# solar_cell.net
KiCad netlist of a schematic drawn in Altium Designer
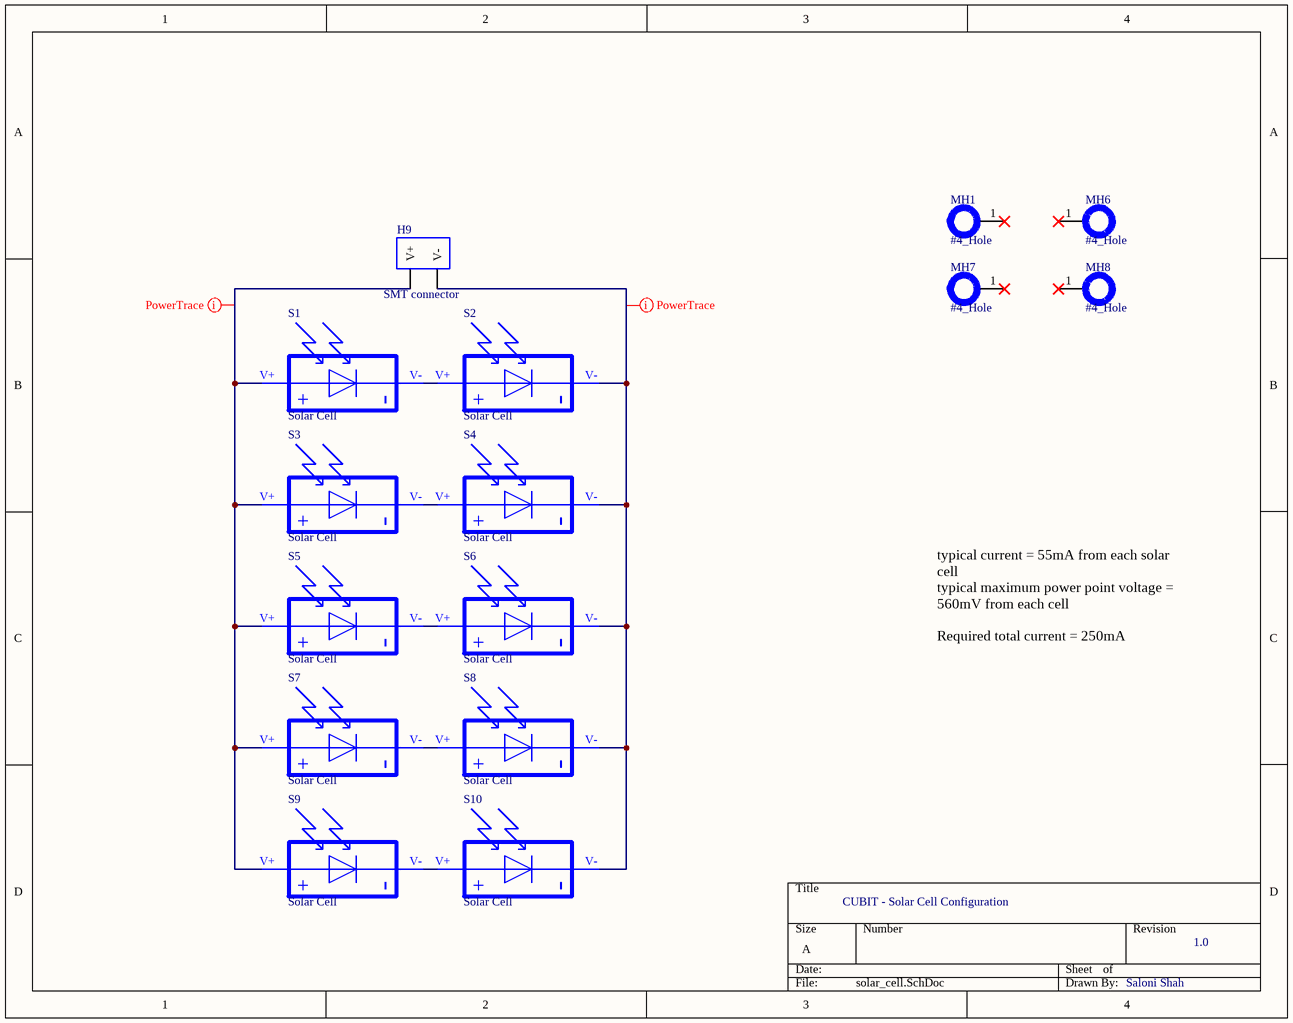
[diagram p0: solar_cell.SchDoc]

(export (version "E")
  (design (tool "Eeschema 10.0.6"))
  (components
    (comp (ref "H9")
      (value "SMT connector")
      (footprint "BAT_CONN")
      (description "2.00mm Pitch")
      (libsource (lib "LPEDT_proj_lib") (part "batt_conn_pad"))
    )
    (comp (ref "MH1")
      (value "#4_Hole")
      (footprint "HOLE_#4")
      (libsource (lib "LPEDT_proj_lib") (part "Mechanical_Hole"))
    )
    (comp (ref "MH6")
      (value "#4_Hole")
      (footprint "HOLE_#4")
      (libsource (lib "LPEDT_proj_lib") (part "Mechanical_Hole"))
    )
    (comp (ref "MH7")
      (value "#4_Hole")
      (footprint "HOLE_#4")
      (libsource (lib "LPEDT_proj_lib") (part "Mechanical_Hole"))
    )
    (comp (ref "MH8")
      (value "#4_Hole")
      (footprint "HOLE_#4")
      (libsource (lib "LPEDT_proj_lib") (part "Mechanical_Hole"))
    )
    (comp (ref "S1")
      (value "Solar Cell")
      (footprint "KXOB25-14X1F")
      (description "Monocrystalline SOLAR CELL 30.7MW 690MV")
      (fields (field (name "MP") "KXOB25-14X1F") (field (name "MF") "ANYSOLAR Ltd"))
      (libsource (lib "LPEDT_proj_lib") (part "KXOB25-14X1F"))
    )
    (comp (ref "S2")
      (value "Solar Cell")
      (footprint "KXOB25-14X1F")
      (description "Monocrystalline SOLAR CELL 30.7MW 690MV")
      (fields (field (name "MP") "KXOB25-14X1F") (field (name "MF") "ANYSOLAR Ltd"))
      (libsource (lib "LPEDT_proj_lib") (part "KXOB25-14X1F"))
    )
    (comp (ref "S3")
      (value "Solar Cell")
      (footprint "KXOB25-14X1F")
      (description "Monocrystalline SOLAR CELL 30.7MW 690MV")
      (fields (field (name "MP") "KXOB25-14X1F") (field (name "MF") "ANYSOLAR Ltd"))
      (libsource (lib "LPEDT_proj_lib") (part "KXOB25-14X1F"))
    )
    (comp (ref "S4")
      (value "Solar Cell")
      (footprint "KXOB25-14X1F")
      (description "Monocrystalline SOLAR CELL 30.7MW 690MV")
      (fields (field (name "MP") "KXOB25-14X1F") (field (name "MF") "ANYSOLAR Ltd"))
      (libsource (lib "LPEDT_proj_lib") (part "KXOB25-14X1F"))
    )
    (comp (ref "S5")
      (value "Solar Cell")
      (footprint "KXOB25-14X1F")
      (description "Monocrystalline SOLAR CELL 30.7MW 690MV")
      (fields (field (name "MP") "KXOB25-14X1F") (field (name "MF") "ANYSOLAR Ltd"))
      (libsource (lib "LPEDT_proj_lib") (part "KXOB25-14X1F"))
    )
    (comp (ref "S6")
      (value "Solar Cell")
      (footprint "KXOB25-14X1F")
      (description "Monocrystalline SOLAR CELL 30.7MW 690MV")
      (fields (field (name "MP") "KXOB25-14X1F") (field (name "MF") "ANYSOLAR Ltd"))
      (libsource (lib "LPEDT_proj_lib") (part "KXOB25-14X1F"))
    )
    (comp (ref "S7")
      (value "Solar Cell")
      (footprint "KXOB25-14X1F")
      (description "Monocrystalline SOLAR CELL 30.7MW 690MV")
      (fields (field (name "MP") "KXOB25-14X1F") (field (name "MF") "ANYSOLAR Ltd"))
      (libsource (lib "LPEDT_proj_lib") (part "KXOB25-14X1F"))
    )
    (comp (ref "S8")
      (value "Solar Cell")
      (footprint "KXOB25-14X1F")
      (description "Monocrystalline SOLAR CELL 30.7MW 690MV")
      (fields (field (name "MP") "KXOB25-14X1F") (field (name "MF") "ANYSOLAR Ltd"))
      (libsource (lib "LPEDT_proj_lib") (part "KXOB25-14X1F"))
    )
    (comp (ref "S9")
      (value "Solar Cell")
      (footprint "KXOB25-14X1F")
      (description "Monocrystalline SOLAR CELL 30.7MW 690MV")
      (fields (field (name "MP") "KXOB25-14X1F") (field (name "MF") "ANYSOLAR Ltd"))
      (libsource (lib "LPEDT_proj_lib") (part "KXOB25-14X1F"))
    )
    (comp (ref "S10")
      (value "Solar Cell")
      (footprint "KXOB25-14X1F")
      (description "Monocrystalline SOLAR CELL 30.7MW 690MV")
      (fields (field (name "MP") "KXOB25-14X1F") (field (name "MF") "ANYSOLAR Ltd"))
      (libsource (lib "LPEDT_proj_lib") (part "KXOB25-14X1F"))
    )
  )
  (nets
    (net (code "1") (name "Net-(H9-PadV+)") (class "Default")
      (node (ref "H9") (pin "V+") (pinfunction "V+_V+") (pintype "passive"))
      (node (ref "S1") (pin "V+") (pintype "power_in"))
      (node (ref "S3") (pin "V+") (pintype "power_in"))
      (node (ref "S5") (pin "V+") (pintype "power_in"))
      (node (ref "S7") (pin "V+") (pintype "power_in"))
      (node (ref "S9") (pin "V+") (pintype "power_in"))
    )
    (net (code "2") (name "Net-(H9-PadV-)") (class "Default")
      (node (ref "H9") (pin "V-") (pinfunction "V-_V-") (pintype "passive"))
      (node (ref "S10") (pin "V-") (pintype "power_in"))
      (node (ref "S2") (pin "V-") (pintype "power_in"))
      (node (ref "S4") (pin "V-") (pintype "power_in"))
      (node (ref "S6") (pin "V-") (pintype "power_in"))
      (node (ref "S8") (pin "V-") (pintype "power_in"))
    )
    (net (code "3") (name "Net-(S1-PadV-)") (class "Default")
      (node (ref "S1") (pin "V-") (pintype "power_in"))
      (node (ref "S2") (pin "V+") (pintype "power_in"))
    )
    (net (code "4") (name "Net-(S3-PadV-)") (class "Default")
      (node (ref "S3") (pin "V-") (pintype "power_in"))
      (node (ref "S4") (pin "V+") (pintype "power_in"))
    )
    (net (code "5") (name "Net-(S5-PadV-)") (class "Default")
      (node (ref "S5") (pin "V-") (pintype "power_in"))
      (node (ref "S6") (pin "V+") (pintype "power_in"))
    )
    (net (code "6") (name "Net-(S7-PadV-)") (class "Default")
      (node (ref "S7") (pin "V-") (pintype "power_in"))
      (node (ref "S8") (pin "V+") (pintype "power_in"))
    )
    (net (code "7") (name "Net-(S10-PadV+)") (class "Default")
      (node (ref "S10") (pin "V+") (pintype "power_in"))
      (node (ref "S9") (pin "V-") (pintype "power_in"))
    )
    (net (code "8") (name "unconnected-(MH1-Pad1)") (class "Default")
      (node (ref "MH1") (pin "1") (pinfunction "1_1") (pintype "passive+no_connect"))
    )
    (net (code "9") (name "unconnected-(MH6-Pad1)") (class "Default")
      (node (ref "MH6") (pin "1") (pinfunction "1_1") (pintype "passive+no_connect"))
    )
    (net (code "10") (name "unconnected-(MH7-Pad1)") (class "Default")
      (node (ref "MH7") (pin "1") (pinfunction "1_1") (pintype "passive+no_connect"))
    )
    (net (code "11") (name "unconnected-(MH8-Pad1)") (class "Default")
      (node (ref "MH8") (pin "1") (pinfunction "1_1") (pintype "passive+no_connect"))
    )
  )
)
